# design.net
KiCad netlist of a schematic drawn in Altium Designer
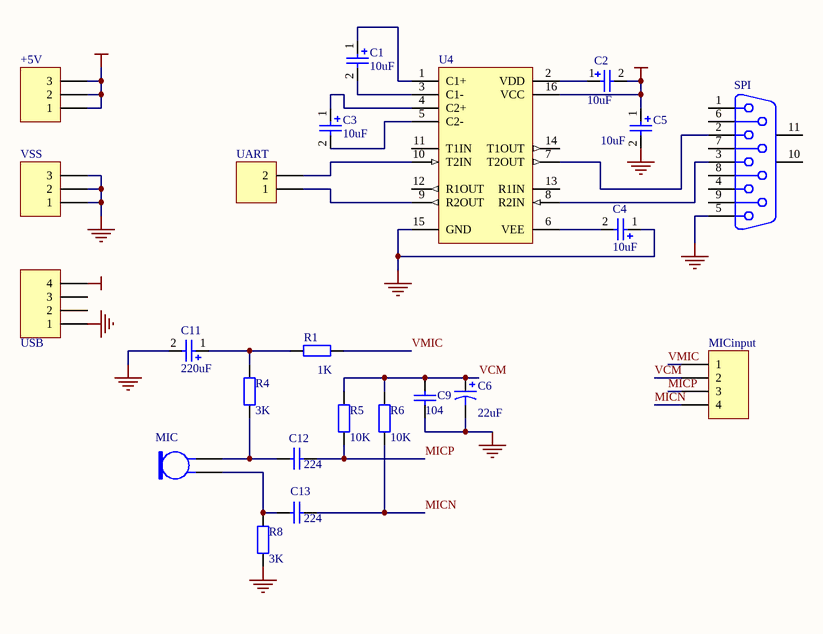
[diagram p0: 原理图.SchDoc]

(export (version "E")
  (design (tool "Eeschema 10.0.6"))
  (components
    (comp (ref "+5V")
      (value "PZ_3")
      (footprint "HDR-3")
      (description "排针——3")
      (fields (field (name "PUBLISHER") "Altium Limited"))
      (libsource (lib "zxcourhc") (part "PZ_3"))
    )
    (comp (ref "C1")
      (value "10uF")
      (footprint "DJDR_4mm")
      (description "电解电容")
      (fields (field (name "Comment") "DJDR") (field (name "PUBLISHER") "Altium Limited"))
      (libsource (lib "zxcourhc") (part "DJDR"))
    )
    (comp (ref "C2")
      (value "10uF")
      (footprint "DJDR_4mm")
      (description "电解电容")
      (fields (field (name "Comment") "DJDR") (field (name "PUBLISHER") "Altium Limited"))
      (libsource (lib "zxcourhc") (part "DJDR"))
    )
    (comp (ref "C3")
      (value "10uF")
      (footprint "DJDR_4mm")
      (description "电解电容")
      (fields (field (name "Comment") "DJDR") (field (name "PUBLISHER") "Altium Limited"))
      (libsource (lib "zxcourhc") (part "DJDR"))
    )
    (comp (ref "C4")
      (value "10uF")
      (footprint "DJDR_4mm")
      (description "电解电容")
      (fields (field (name "Comment") "DJDR") (field (name "PUBLISHER") "Altium Limited"))
      (libsource (lib "zxcourhc") (part "DJDR"))
    )
    (comp (ref "C5")
      (value "10uF")
      (footprint "DJDR_4mm")
      (description "电解电容")
      (fields (field (name "Comment") "DJDR") (field (name "PUBLISHER") "Altium Limited"))
      (libsource (lib "zxcourhc") (part "DJDR"))
    )
    (comp (ref "C6")
      (value "22uF")
      (footprint "zxcourhc:C-DJ-4")
      (description "Polarized Capacitor (Radial)")
      (fields (field (name "Comment") "Cap Pol1") (field (name "PUBLISHER") "Altium Limited"))
      (libsource (lib "Miscellaneous Devices") (part "Cap Pol1"))
    )
    (comp (ref "C9")
      (value "104")
      (footprint "zxcourhc:CPDR")
      (description "Capacitor")
      (fields (field (name "Comment") "Cap") (field (name "PUBLISHER") "Altium Limited"))
      (libsource (lib "Miscellaneous Devices") (part "Cap"))
    )
    (comp (ref "C11")
      (value "220uF")
      (footprint "DJDR_4mm")
      (description "电解电容")
      (fields (field (name "Comment") "DJDR") (field (name "PUBLISHER") "Altium Limited"))
      (libsource (lib "zxcourhc") (part "DJDR"))
    )
    (comp (ref "C12")
      (value "224")
      (footprint "zxcourhc:CPDR")
      (description "Capacitor")
      (fields (field (name "Comment") "Cap") (field (name "PUBLISHER") "Altium Limited"))
      (libsource (lib "Miscellaneous Devices") (part "Cap"))
    )
    (comp (ref "C13")
      (value "224")
      (footprint "zxcourhc:CPDR")
      (description "Capacitor")
      (fields (field (name "Comment") "Cap") (field (name "PUBLISHER") "Altium Limited"))
      (libsource (lib "Miscellaneous Devices") (part "Cap"))
    )
    (comp (ref "MIC")
      (value "MKF")
      (footprint "zxcourhc:HDR-2")
      (description "麦克风")
      (fields (field (name "PUBLISHER") "Altium Limited"))
      (libsource (lib "zxcourhc") (part "MKF"))
    )
    (comp (ref "MICinput")
      (value "PZ_4")
      (footprint "HDR-4")
      (description "排针——4")
      (fields (field (name "PUBLISHER") "Altium Limited"))
      (libsource (lib "zxcourhc") (part "PZ_4"))
    )
    (comp (ref "R1")
      (value "1K")
      (footprint "zxcourhc:RSE")
      (description "Resistor")
      (fields (field (name "Comment") "Res2") (field (name "PUBLISHER") "Altium Limited"))
      (libsource (lib "") (part "Res2_1"))
    )
    (comp (ref "R4")
      (value "3K")
      (footprint "zxcourhc:RSE")
      (description "Resistor")
      (fields (field (name "Comment") "Res2") (field (name "PUBLISHER") "Altium Limited"))
      (libsource (lib "Miscellaneous Devices") (part "Res2"))
    )
    (comp (ref "R5")
      (value "10K")
      (footprint "zxcourhc:RSE")
      (description "Resistor")
      (fields (field (name "Comment") "Res2") (field (name "PUBLISHER") "Altium Limited"))
      (libsource (lib "Miscellaneous Devices") (part "Res2"))
    )
    (comp (ref "R6")
      (value "10K")
      (footprint "zxcourhc:RSE")
      (description "Resistor")
      (fields (field (name "Comment") "Res2") (field (name "PUBLISHER") "Altium Limited"))
      (libsource (lib "Miscellaneous Devices") (part "Res2"))
    )
    (comp (ref "R8")
      (value "3K")
      (footprint "zxcourhc:RSE")
      (description "Resistor")
      (fields (field (name "Comment") "Res2") (field (name "PUBLISHER") "Altium Limited"))
      (libsource (lib "Miscellaneous Devices") (part "Res2"))
    )
    (comp (ref "SPI")
      (value "CKT_9")
      (footprint "COM-9")
      (description "9针串口头_母")
      (fields (field (name "PUBLISHER") "Altium Limited"))
      (libsource (lib "zxcourhc") (part "CKT_9"))
    )
    (comp (ref "U4")
      (value "MAX232ACPE")
      (footprint "zxcourhc:DIP-16")
      (description "+5V Powered, Multi-Channel RS-232 Driver/Receiver")
      (fields (field (name "PUBLISHER") "Altium Limited"))
      (libsource (lib "Maxim Communication Transceiver") (part "MAX232ACPE"))
    )
    (comp (ref "UART")
      (value "PZ_2")
      (footprint "HDR-2")
      (description "排针——2")
      (fields (field (name "PUBLISHER") "Altium Limited"))
      (libsource (lib "zxcourhc") (part "PZ_2"))
    )
    (comp (ref "USB")
      (value "PZ_4")
      (footprint "zxcourhc:USB - duplicate")
      (description "排针——4")
      (fields (field (name "PUBLISHER") "Altium Limited"))
      (libsource (lib "") (part "PZ_4_1"))
    )
    (comp (ref "VSS")
      (value "PZ_3")
      (footprint "HDR-3")
      (description "排针——3")
      (fields (field (name "PUBLISHER") "Altium Limited"))
      (libsource (lib "zxcourhc") (part "PZ_3"))
    )
  )
  (nets
    (net (code "1") (name "/MICN") (class "Default")
      (node (ref "C13") (pin "2") (pinfunction "2_2") (pintype "passive"))
      (node (ref "MICinput") (pin "4") (pinfunction "4_4") (pintype "passive"))
      (node (ref "R6") (pin "1") (pinfunction "1_1") (pintype "passive"))
    )
    (net (code "2") (name "/MICP") (class "Default")
      (node (ref "C12") (pin "2") (pinfunction "2_2") (pintype "passive"))
      (node (ref "MICinput") (pin "3") (pinfunction "3_3") (pintype "passive"))
      (node (ref "R5") (pin "1") (pinfunction "1_1") (pintype "passive"))
    )
    (net (code "3") (name "/VCM") (class "Default")
      (node (ref "C6") (pin "1") (pinfunction "1_1") (pintype "passive"))
      (node (ref "C9") (pin "2") (pinfunction "2_2") (pintype "passive"))
      (node (ref "MICinput") (pin "2") (pinfunction "2_2") (pintype "passive"))
      (node (ref "R5") (pin "2") (pinfunction "2_2") (pintype "passive"))
      (node (ref "R6") (pin "2") (pinfunction "2_2") (pintype "passive"))
    )
    (net (code "4") (name "/VMIC") (class "Default")
      (node (ref "MICinput") (pin "1") (pinfunction "1_1") (pintype "passive"))
      (node (ref "R1") (pin "2") (pinfunction "2_2") (pintype "passive"))
    )
    (net (code "5") (name "GND") (class "Default")
      (node (ref "C11") (pin "2") (pinfunction "2_2") (pintype "passive"))
      (node (ref "C4") (pin "1") (pinfunction "1_1") (pintype "passive"))
      (node (ref "C5") (pin "2") (pinfunction "2_2") (pintype "passive"))
      (node (ref "C6") (pin "2") (pinfunction "2_2") (pintype "passive"))
      (node (ref "C9") (pin "1") (pinfunction "1_1") (pintype "passive"))
      (node (ref "R8") (pin "1") (pinfunction "1_1") (pintype "passive"))
      (node (ref "SPI") (pin "5") (pinfunction "5_5") (pintype "passive"))
      (node (ref "U4") (pin "15") (pinfunction "GND_15") (pintype "power_in"))
      (node (ref "USB") (pin "1") (pinfunction "1_1") (pintype "passive"))
      (node (ref "VSS") (pin "1") (pinfunction "1_1") (pintype "passive"))
      (node (ref "VSS") (pin "2") (pinfunction "2_2") (pintype "passive"))
      (node (ref "VSS") (pin "3") (pinfunction "3_3") (pintype "passive"))
    )
    (net (code "6") (name "Net-(C11-Pad1)") (class "Default")
      (node (ref "C11") (pin "1") (pinfunction "1_1") (pintype "passive"))
      (node (ref "R1") (pin "1") (pinfunction "1_1") (pintype "passive"))
      (node (ref "R4") (pin "2") (pinfunction "2_2") (pintype "passive"))
    )
    (net (code "7") (name "Net-(C13-Pad1)") (class "Default")
      (node (ref "C13") (pin "1") (pinfunction "1_1") (pintype "passive"))
      (node (ref "MIC") (pin "2") (pinfunction "2_2") (pintype "passive"))
      (node (ref "R8") (pin "2") (pinfunction "2_2") (pintype "passive"))
    )
    (net (code "8") (name "Net-(MIC-+)") (class "Default")
      (node (ref "C12") (pin "1") (pinfunction "1_1") (pintype "passive"))
      (node (ref "MIC") (pin "1") (pinfunction "+_1") (pintype "passive"))
      (node (ref "R4") (pin "1") (pinfunction "1_1") (pintype "passive"))
    )
    (net (code "9") (name "Net-(U4-C1+)") (class "Default")
      (node (ref "C1") (pin "1") (pinfunction "1_1") (pintype "passive"))
      (node (ref "U4") (pin "1") (pinfunction "C1+_1") (pintype "passive"))
    )
    (net (code "10") (name "Net-(U4-C1-)") (class "Default")
      (node (ref "C1") (pin "2") (pinfunction "2_2") (pintype "passive"))
      (node (ref "U4") (pin "3") (pinfunction "C1-_3") (pintype "passive"))
    )
    (net (code "11") (name "Net-(U4-C2+)") (class "Default")
      (node (ref "C3") (pin "1") (pinfunction "1_1") (pintype "passive"))
      (node (ref "U4") (pin "4") (pinfunction "C2+_4") (pintype "passive"))
    )
    (net (code "12") (name "Net-(U4-C2-)") (class "Default")
      (node (ref "C3") (pin "2") (pinfunction "2_2") (pintype "passive"))
      (node (ref "U4") (pin "5") (pinfunction "C2-_5") (pintype "passive"))
    )
    (net (code "13") (name "Net-(U4-R2IN)") (class "Default")
      (node (ref "SPI") (pin "3") (pinfunction "3_3") (pintype "passive"))
      (node (ref "U4") (pin "8") (pinfunction "R2IN_8") (pintype "input"))
    )
    (net (code "14") (name "Net-(U4-R2OUT)") (class "Default")
      (node (ref "U4") (pin "9") (pinfunction "R2OUT_9") (pintype "output"))
      (node (ref "UART") (pin "1") (pinfunction "1_1") (pintype "passive"))
    )
    (net (code "15") (name "Net-(U4-T2IN)") (class "Default")
      (node (ref "U4") (pin "10") (pinfunction "T2IN_10") (pintype "input"))
      (node (ref "UART") (pin "2") (pinfunction "2_2") (pintype "passive"))
    )
    (net (code "16") (name "Net-(U4-T2OUT)") (class "Default")
      (node (ref "SPI") (pin "2") (pinfunction "2_2") (pintype "passive"))
      (node (ref "U4") (pin "7") (pinfunction "T2OUT_7") (pintype "output"))
    )
    (net (code "17") (name "Net-(U4-VDD)") (class "Default")
      (node (ref "C2") (pin "1") (pinfunction "1_1") (pintype "passive"))
      (node (ref "U4") (pin "2") (pinfunction "VDD_2") (pintype "power_in"))
    )
    (net (code "18") (name "Net-(U4-VEE)") (class "Default")
      (node (ref "C4") (pin "2") (pinfunction "2_2") (pintype "passive"))
      (node (ref "U4") (pin "6") (pinfunction "VEE_6") (pintype "power_in"))
    )
    (net (code "19") (name "VCC") (class "Default")
      (node (ref "+5V") (pin "1") (pinfunction "1_1") (pintype "passive"))
      (node (ref "+5V") (pin "2") (pinfunction "2_2") (pintype "passive"))
      (node (ref "+5V") (pin "3") (pinfunction "3_3") (pintype "passive"))
      (node (ref "C2") (pin "2") (pinfunction "2_2") (pintype "passive"))
      (node (ref "C5") (pin "1") (pinfunction "1_1") (pintype "passive"))
      (node (ref "U4") (pin "16") (pinfunction "VCC_16") (pintype "power_in"))
      (node (ref "USB") (pin "4") (pinfunction "4_4") (pintype "passive"))
    )
    (net (code "20") (name "unconnected-(SPI-MH1-Pad10)") (class "Default")
      (node (ref "SPI") (pin "10") (pinfunction "MH1_10") (pintype "passive"))
    )
    (net (code "21") (name "unconnected-(SPI-MH2-Pad11)") (class "Default")
      (node (ref "SPI") (pin "11") (pinfunction "MH2_11") (pintype "passive"))
    )
    (net (code "22") (name "unconnected-(SPI-Pad1)") (class "Default")
      (node (ref "SPI") (pin "1") (pinfunction "1_1") (pintype "passive"))
    )
    (net (code "23") (name "unconnected-(SPI-Pad4)") (class "Default")
      (node (ref "SPI") (pin "4") (pinfunction "4_4") (pintype "passive"))
    )
    (net (code "24") (name "unconnected-(SPI-Pad6)") (class "Default")
      (node (ref "SPI") (pin "6") (pinfunction "6_6") (pintype "passive"))
    )
    (net (code "25") (name "unconnected-(SPI-Pad7)") (class "Default")
      (node (ref "SPI") (pin "7") (pinfunction "7_7") (pintype "passive"))
    )
    (net (code "26") (name "unconnected-(SPI-Pad8)") (class "Default")
      (node (ref "SPI") (pin "8") (pinfunction "8_8") (pintype "passive"))
    )
    (net (code "27") (name "unconnected-(SPI-Pad9)") (class "Default")
      (node (ref "SPI") (pin "9") (pinfunction "9_9") (pintype "passive"))
    )
    (net (code "28") (name "unconnected-(U4-R1IN-Pad13)") (class "Default")
      (node (ref "U4") (pin "13") (pinfunction "R1IN_13") (pintype "passive"))
    )
    (net (code "29") (name "unconnected-(U4-R1OUT-Pad12)") (class "Default")
      (node (ref "U4") (pin "12") (pinfunction "R1OUT_12") (pintype "output"))
    )
    (net (code "30") (name "unconnected-(U4-T1IN-Pad11)") (class "Default")
      (node (ref "U4") (pin "11") (pinfunction "T1IN_11") (pintype "passive"))
    )
    (net (code "31") (name "unconnected-(U4-T1OUT-Pad14)") (class "Default")
      (node (ref "U4") (pin "14") (pinfunction "T1OUT_14") (pintype "output"))
    )
    (net (code "32") (name "unconnected-(USB-Pad2)") (class "Default")
      (node (ref "USB") (pin "2") (pinfunction "2_2") (pintype "passive"))
    )
    (net (code "33") (name "unconnected-(USB-Pad3)") (class "Default")
      (node (ref "USB") (pin "3") (pinfunction "3_3") (pintype "passive"))
    )
  )
)
